# Backlight.net
KiCad netlist of a schematic drawn in Altium Designer
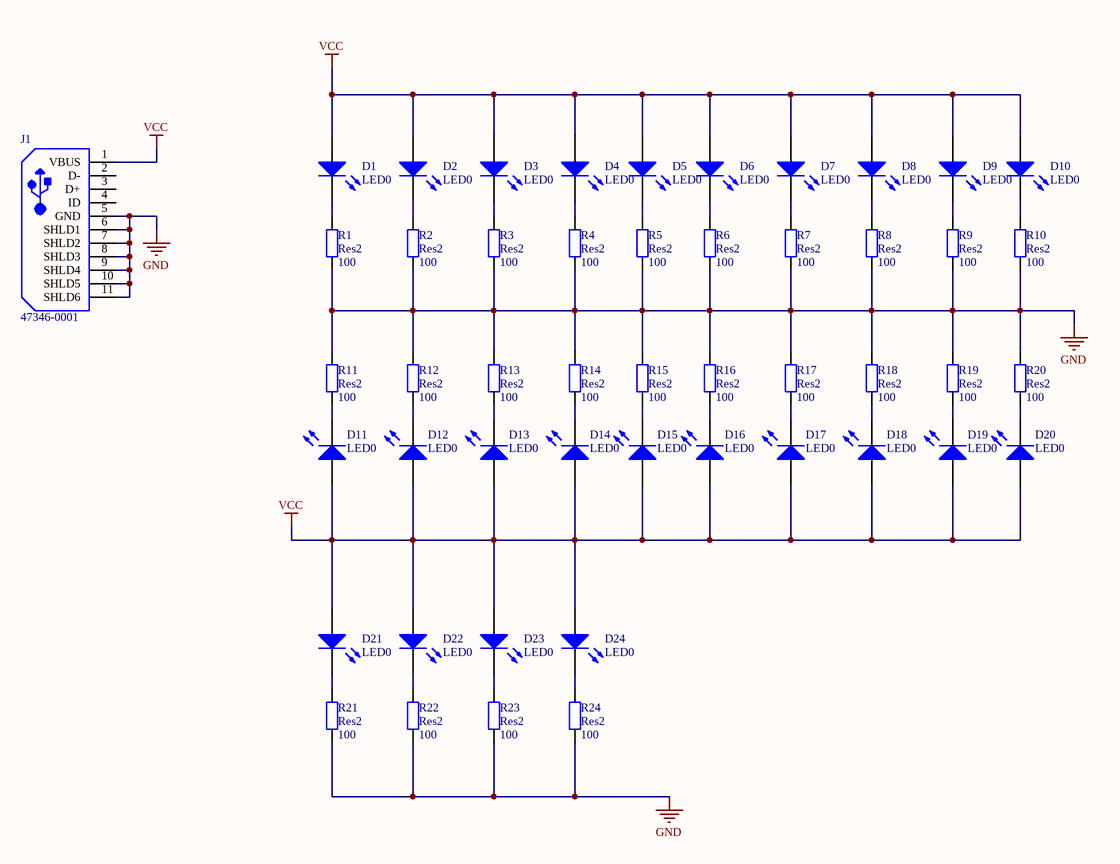
[diagram p0: Backlight.SchDoc]

(export (version "E")
  (design (tool "Eeschema 10.0.6"))
  (components
    (comp (ref "D1")
      (value "LED0")
      (footprint "DIOC2012X06N")
      (description "Typical INFRARED GaAs LED")
      (fields (field (name "PUBLISHER") "Altium Limited"))
      (libsource (lib "Miscellaneous Devices") (part "LED0"))
    )
    (comp (ref "D2")
      (value "LED0")
      (footprint "DIOC2012X06N")
      (description "Typical INFRARED GaAs LED")
      (fields (field (name "PUBLISHER") "Altium Limited"))
      (libsource (lib "Miscellaneous Devices") (part "LED0"))
    )
    (comp (ref "D3")
      (value "LED0")
      (footprint "DIOC2012X06N")
      (description "Typical INFRARED GaAs LED")
      (fields (field (name "PUBLISHER") "Altium Limited"))
      (libsource (lib "Miscellaneous Devices") (part "LED0"))
    )
    (comp (ref "D4")
      (value "LED0")
      (footprint "DIOC2012X06N")
      (description "Typical INFRARED GaAs LED")
      (fields (field (name "PUBLISHER") "Altium Limited"))
      (libsource (lib "Miscellaneous Devices") (part "LED0"))
    )
    (comp (ref "D5")
      (value "LED0")
      (footprint "DIOC2012X06N")
      (description "Typical INFRARED GaAs LED")
      (fields (field (name "PUBLISHER") "Altium Limited"))
      (libsource (lib "Miscellaneous Devices") (part "LED0"))
    )
    (comp (ref "D6")
      (value "LED0")
      (footprint "DIOC2012X06N")
      (description "Typical INFRARED GaAs LED")
      (fields (field (name "PUBLISHER") "Altium Limited"))
      (libsource (lib "Miscellaneous Devices") (part "LED0"))
    )
    (comp (ref "D7")
      (value "LED0")
      (footprint "DIOC2012X06N")
      (description "Typical INFRARED GaAs LED")
      (fields (field (name "PUBLISHER") "Altium Limited"))
      (libsource (lib "Miscellaneous Devices") (part "LED0"))
    )
    (comp (ref "D8")
      (value "LED0")
      (footprint "DIOC2012X06N")
      (description "Typical INFRARED GaAs LED")
      (fields (field (name "PUBLISHER") "Altium Limited"))
      (libsource (lib "Miscellaneous Devices") (part "LED0"))
    )
    (comp (ref "D9")
      (value "LED0")
      (footprint "DIOC2012X06N")
      (description "Typical INFRARED GaAs LED")
      (fields (field (name "PUBLISHER") "Altium Limited"))
      (libsource (lib "Miscellaneous Devices") (part "LED0"))
    )
    (comp (ref "D10")
      (value "LED0")
      (footprint "DIOC2012X06N")
      (description "Typical INFRARED GaAs LED")
      (fields (field (name "PUBLISHER") "Altium Limited"))
      (libsource (lib "Miscellaneous Devices") (part "LED0"))
    )
    (comp (ref "D11")
      (value "LED0")
      (footprint "DIOC2012X06N")
      (description "Typical INFRARED GaAs LED")
      (fields (field (name "PUBLISHER") "Altium Limited"))
      (libsource (lib "Miscellaneous Devices") (part "LED0"))
    )
    (comp (ref "D12")
      (value "LED0")
      (footprint "DIOC2012X06N")
      (description "Typical INFRARED GaAs LED")
      (fields (field (name "PUBLISHER") "Altium Limited"))
      (libsource (lib "Miscellaneous Devices") (part "LED0"))
    )
    (comp (ref "D13")
      (value "LED0")
      (footprint "DIOC2012X06N")
      (description "Typical INFRARED GaAs LED")
      (fields (field (name "PUBLISHER") "Altium Limited"))
      (libsource (lib "Miscellaneous Devices") (part "LED0"))
    )
    (comp (ref "D14")
      (value "LED0")
      (footprint "DIOC2012X06N")
      (description "Typical INFRARED GaAs LED")
      (fields (field (name "PUBLISHER") "Altium Limited"))
      (libsource (lib "Miscellaneous Devices") (part "LED0"))
    )
    (comp (ref "D15")
      (value "LED0")
      (footprint "DIOC2012X06N")
      (description "Typical INFRARED GaAs LED")
      (fields (field (name "PUBLISHER") "Altium Limited"))
      (libsource (lib "Miscellaneous Devices") (part "LED0"))
    )
    (comp (ref "D16")
      (value "LED0")
      (footprint "DIOC2012X06N")
      (description "Typical INFRARED GaAs LED")
      (fields (field (name "PUBLISHER") "Altium Limited"))
      (libsource (lib "Miscellaneous Devices") (part "LED0"))
    )
    (comp (ref "D17")
      (value "LED0")
      (footprint "DIOC2012X06N")
      (description "Typical INFRARED GaAs LED")
      (fields (field (name "PUBLISHER") "Altium Limited"))
      (libsource (lib "Miscellaneous Devices") (part "LED0"))
    )
    (comp (ref "D18")
      (value "LED0")
      (footprint "DIOC2012X06N")
      (description "Typical INFRARED GaAs LED")
      (fields (field (name "PUBLISHER") "Altium Limited"))
      (libsource (lib "Miscellaneous Devices") (part "LED0"))
    )
    (comp (ref "D19")
      (value "LED0")
      (footprint "DIOC2012X06N")
      (description "Typical INFRARED GaAs LED")
      (fields (field (name "PUBLISHER") "Altium Limited"))
      (libsource (lib "Miscellaneous Devices") (part "LED0"))
    )
    (comp (ref "D20")
      (value "LED0")
      (footprint "DIOC2012X06N")
      (description "Typical INFRARED GaAs LED")
      (fields (field (name "PUBLISHER") "Altium Limited"))
      (libsource (lib "Miscellaneous Devices") (part "LED0"))
    )
    (comp (ref "D21")
      (value "LED0")
      (footprint "DIOC2012X06N")
      (description "Typical INFRARED GaAs LED")
      (fields (field (name "PUBLISHER") "Altium Limited"))
      (libsource (lib "Miscellaneous Devices") (part "LED0"))
    )
    (comp (ref "D22")
      (value "LED0")
      (footprint "DIOC2012X06N")
      (description "Typical INFRARED GaAs LED")
      (fields (field (name "PUBLISHER") "Altium Limited"))
      (libsource (lib "Miscellaneous Devices") (part "LED0"))
    )
    (comp (ref "D23")
      (value "LED0")
      (footprint "DIOC2012X06N")
      (description "Typical INFRARED GaAs LED")
      (fields (field (name "PUBLISHER") "Altium Limited"))
      (libsource (lib "Miscellaneous Devices") (part "LED0"))
    )
    (comp (ref "D24")
      (value "LED0")
      (footprint "DIOC2012X06N")
      (description "Typical INFRARED GaAs LED")
      (fields (field (name "PUBLISHER") "Altium Limited"))
      (libsource (lib "Miscellaneous Devices") (part "LED0"))
    )
    (comp (ref "J1")
      (value "47346-0001")
      (footprint "MOLX-47346-0001-5_V")
      (description "Micro-USB B Receptacle with Flange, -30 to 85 degC, 5-Pin SMD, RoHS, Tape and Reel")
      (fields (field (name "MANUFACTURER") "Molex"))
      (libsource (lib "Altium Content Vault") (part "MOLX-47346-0001-5"))
    )
    (comp (ref "R1")
      (value "Res2")
      (footprint "RESC2012X06N")
      (description "Resistor")
      (fields (field (name "ALTIUM_VALUE") "100") (field (name "PUBLISHER") "Altium Limited"))
      (libsource (lib "") (part "Res2_1"))
    )
    (comp (ref "R2")
      (value "Res2")
      (footprint "RESC2012X06N")
      (description "Resistor")
      (fields (field (name "ALTIUM_VALUE") "100") (field (name "PUBLISHER") "Altium Limited"))
      (libsource (lib "") (part "Res2_1"))
    )
    (comp (ref "R3")
      (value "Res2")
      (footprint "RESC2012X06N")
      (description "Resistor")
      (fields (field (name "ALTIUM_VALUE") "100") (field (name "PUBLISHER") "Altium Limited"))
      (libsource (lib "") (part "Res2_1"))
    )
    (comp (ref "R4")
      (value "Res2")
      (footprint "RESC2012X06N")
      (description "Resistor")
      (fields (field (name "ALTIUM_VALUE") "100") (field (name "PUBLISHER") "Altium Limited"))
      (libsource (lib "") (part "Res2_1"))
    )
    (comp (ref "R5")
      (value "Res2")
      (footprint "RESC2012X06N")
      (description "Resistor")
      (fields (field (name "ALTIUM_VALUE") "100") (field (name "PUBLISHER") "Altium Limited"))
      (libsource (lib "") (part "Res2_1"))
    )
    (comp (ref "R6")
      (value "Res2")
      (footprint "RESC2012X06N")
      (description "Resistor")
      (fields (field (name "ALTIUM_VALUE") "100") (field (name "PUBLISHER") "Altium Limited"))
      (libsource (lib "") (part "Res2_1"))
    )
    (comp (ref "R7")
      (value "Res2")
      (footprint "RESC2012X06N")
      (description "Resistor")
      (fields (field (name "ALTIUM_VALUE") "100") (field (name "PUBLISHER") "Altium Limited"))
      (libsource (lib "") (part "Res2_1"))
    )
    (comp (ref "R8")
      (value "Res2")
      (footprint "RESC2012X06N")
      (description "Resistor")
      (fields (field (name "ALTIUM_VALUE") "100") (field (name "PUBLISHER") "Altium Limited"))
      (libsource (lib "") (part "Res2_1"))
    )
    (comp (ref "R9")
      (value "Res2")
      (footprint "RESC2012X06N")
      (description "Resistor")
      (fields (field (name "ALTIUM_VALUE") "100") (field (name "PUBLISHER") "Altium Limited"))
      (libsource (lib "") (part "Res2_1"))
    )
    (comp (ref "R10")
      (value "Res2")
      (footprint "RESC2012X06N")
      (description "Resistor")
      (fields (field (name "ALTIUM_VALUE") "100") (field (name "PUBLISHER") "Altium Limited"))
      (libsource (lib "") (part "Res2_1"))
    )
    (comp (ref "R11")
      (value "Res2")
      (footprint "RESC2012X06N")
      (description "Resistor")
      (fields (field (name "ALTIUM_VALUE") "100") (field (name "PUBLISHER") "Altium Limited"))
      (libsource (lib "Miscellaneous Devices") (part "Res2"))
    )
    (comp (ref "R12")
      (value "Res2")
      (footprint "RESC2012X06N")
      (description "Resistor")
      (fields (field (name "ALTIUM_VALUE") "100") (field (name "PUBLISHER") "Altium Limited"))
      (libsource (lib "Miscellaneous Devices") (part "Res2"))
    )
    (comp (ref "R13")
      (value "Res2")
      (footprint "RESC2012X06N")
      (description "Resistor")
      (fields (field (name "ALTIUM_VALUE") "100") (field (name "PUBLISHER") "Altium Limited"))
      (libsource (lib "Miscellaneous Devices") (part "Res2"))
    )
    (comp (ref "R14")
      (value "Res2")
      (footprint "RESC2012X06N")
      (description "Resistor")
      (fields (field (name "ALTIUM_VALUE") "100") (field (name "PUBLISHER") "Altium Limited"))
      (libsource (lib "Miscellaneous Devices") (part "Res2"))
    )
    (comp (ref "R15")
      (value "Res2")
      (footprint "RESC2012X06N")
      (description "Resistor")
      (fields (field (name "ALTIUM_VALUE") "100") (field (name "PUBLISHER") "Altium Limited"))
      (libsource (lib "Miscellaneous Devices") (part "Res2"))
    )
    (comp (ref "R16")
      (value "Res2")
      (footprint "RESC2012X06N")
      (description "Resistor")
      (fields (field (name "ALTIUM_VALUE") "100") (field (name "PUBLISHER") "Altium Limited"))
      (libsource (lib "Miscellaneous Devices") (part "Res2"))
    )
    (comp (ref "R17")
      (value "Res2")
      (footprint "RESC2012X06N")
      (description "Resistor")
      (fields (field (name "ALTIUM_VALUE") "100") (field (name "PUBLISHER") "Altium Limited"))
      (libsource (lib "Miscellaneous Devices") (part "Res2"))
    )
    (comp (ref "R18")
      (value "Res2")
      (footprint "RESC2012X06N")
      (description "Resistor")
      (fields (field (name "ALTIUM_VALUE") "100") (field (name "PUBLISHER") "Altium Limited"))
      (libsource (lib "Miscellaneous Devices") (part "Res2"))
    )
    (comp (ref "R19")
      (value "Res2")
      (footprint "RESC2012X06N")
      (description "Resistor")
      (fields (field (name "ALTIUM_VALUE") "100") (field (name "PUBLISHER") "Altium Limited"))
      (libsource (lib "Miscellaneous Devices") (part "Res2"))
    )
    (comp (ref "R20")
      (value "Res2")
      (footprint "RESC2012X06N")
      (description "Resistor")
      (fields (field (name "ALTIUM_VALUE") "100") (field (name "PUBLISHER") "Altium Limited"))
      (libsource (lib "Miscellaneous Devices") (part "Res2"))
    )
    (comp (ref "R21")
      (value "Res2")
      (footprint "RESC2012X06N")
      (description "Resistor")
      (fields (field (name "ALTIUM_VALUE") "100") (field (name "PUBLISHER") "Altium Limited"))
      (libsource (lib "") (part "Res2_1"))
    )
    (comp (ref "R22")
      (value "Res2")
      (footprint "RESC2012X06N")
      (description "Resistor")
      (fields (field (name "ALTIUM_VALUE") "100") (field (name "PUBLISHER") "Altium Limited"))
      (libsource (lib "") (part "Res2_1"))
    )
    (comp (ref "R23")
      (value "Res2")
      (footprint "RESC2012X06N")
      (description "Resistor")
      (fields (field (name "ALTIUM_VALUE") "100") (field (name "PUBLISHER") "Altium Limited"))
      (libsource (lib "") (part "Res2_1"))
    )
    (comp (ref "R24")
      (value "Res2")
      (footprint "RESC2012X06N")
      (description "Resistor")
      (fields (field (name "ALTIUM_VALUE") "100") (field (name "PUBLISHER") "Altium Limited"))
      (libsource (lib "") (part "Res2_1"))
    )
  )
  (nets
    (net (code "1") (name "GND") (class "Default")
      (node (ref "J1") (pin "10") (pinfunction "SHLD5_10") (pintype "passive"))
      (node (ref "J1") (pin "11") (pinfunction "SHLD6_11") (pintype "passive"))
      (node (ref "J1") (pin "5") (pinfunction "GND_5") (pintype "passive"))
      (node (ref "J1") (pin "6") (pinfunction "SHLD1_6") (pintype "passive"))
      (node (ref "J1") (pin "7") (pinfunction "SHLD2_7") (pintype "passive"))
      (node (ref "J1") (pin "8") (pinfunction "SHLD3_8") (pintype "passive"))
      (node (ref "J1") (pin "9") (pinfunction "SHLD4_9") (pintype "passive"))
      (node (ref "R1") (pin "1") (pinfunction "1_1") (pintype "passive"))
      (node (ref "R10") (pin "1") (pinfunction "1_1") (pintype "passive"))
      (node (ref "R11") (pin "1") (pinfunction "1_1") (pintype "passive"))
      (node (ref "R12") (pin "1") (pinfunction "1_1") (pintype "passive"))
      (node (ref "R13") (pin "1") (pinfunction "1_1") (pintype "passive"))
      (node (ref "R14") (pin "1") (pinfunction "1_1") (pintype "passive"))
      (node (ref "R15") (pin "1") (pinfunction "1_1") (pintype "passive"))
      (node (ref "R16") (pin "1") (pinfunction "1_1") (pintype "passive"))
      (node (ref "R17") (pin "1") (pinfunction "1_1") (pintype "passive"))
      (node (ref "R18") (pin "1") (pinfunction "1_1") (pintype "passive"))
      (node (ref "R19") (pin "1") (pinfunction "1_1") (pintype "passive"))
      (node (ref "R2") (pin "1") (pinfunction "1_1") (pintype "passive"))
      (node (ref "R20") (pin "1") (pinfunction "1_1") (pintype "passive"))
      (node (ref "R21") (pin "1") (pinfunction "1_1") (pintype "passive"))
      (node (ref "R22") (pin "1") (pinfunction "1_1") (pintype "passive"))
      (node (ref "R23") (pin "1") (pinfunction "1_1") (pintype "passive"))
      (node (ref "R24") (pin "1") (pinfunction "1_1") (pintype "passive"))
      (node (ref "R3") (pin "1") (pinfunction "1_1") (pintype "passive"))
      (node (ref "R4") (pin "1") (pinfunction "1_1") (pintype "passive"))
      (node (ref "R5") (pin "1") (pinfunction "1_1") (pintype "passive"))
      (node (ref "R6") (pin "1") (pinfunction "1_1") (pintype "passive"))
      (node (ref "R7") (pin "1") (pinfunction "1_1") (pintype "passive"))
      (node (ref "R8") (pin "1") (pinfunction "1_1") (pintype "passive"))
      (node (ref "R9") (pin "1") (pinfunction "1_1") (pintype "passive"))
    )
    (net (code "2") (name "Net-(D1-K)") (class "Default")
      (node (ref "D1") (pin "2") (pinfunction "K_2") (pintype "passive"))
      (node (ref "R1") (pin "2") (pinfunction "2_2") (pintype "passive"))
    )
    (net (code "3") (name "Net-(D2-K)") (class "Default")
      (node (ref "D2") (pin "2") (pinfunction "K_2") (pintype "passive"))
      (node (ref "R2") (pin "2") (pinfunction "2_2") (pintype "passive"))
    )
    (net (code "4") (name "Net-(D3-K)") (class "Default")
      (node (ref "D3") (pin "2") (pinfunction "K_2") (pintype "passive"))
      (node (ref "R3") (pin "2") (pinfunction "2_2") (pintype "passive"))
    )
    (net (code "5") (name "Net-(D4-K)") (class "Default")
      (node (ref "D4") (pin "2") (pinfunction "K_2") (pintype "passive"))
      (node (ref "R4") (pin "2") (pinfunction "2_2") (pintype "passive"))
    )
    (net (code "6") (name "Net-(D5-K)") (class "Default")
      (node (ref "D5") (pin "2") (pinfunction "K_2") (pintype "passive"))
      (node (ref "R5") (pin "2") (pinfunction "2_2") (pintype "passive"))
    )
    (net (code "7") (name "Net-(D6-K)") (class "Default")
      (node (ref "D6") (pin "2") (pinfunction "K_2") (pintype "passive"))
      (node (ref "R6") (pin "2") (pinfunction "2_2") (pintype "passive"))
    )
    (net (code "8") (name "Net-(D7-K)") (class "Default")
      (node (ref "D7") (pin "2") (pinfunction "K_2") (pintype "passive"))
      (node (ref "R7") (pin "2") (pinfunction "2_2") (pintype "passive"))
    )
    (net (code "9") (name "Net-(D8-K)") (class "Default")
      (node (ref "D8") (pin "2") (pinfunction "K_2") (pintype "passive"))
      (node (ref "R8") (pin "2") (pinfunction "2_2") (pintype "passive"))
    )
    (net (code "10") (name "Net-(D9-K)") (class "Default")
      (node (ref "D9") (pin "2") (pinfunction "K_2") (pintype "passive"))
      (node (ref "R9") (pin "2") (pinfunction "2_2") (pintype "passive"))
    )
    (net (code "11") (name "Net-(D10-K)") (class "Default")
      (node (ref "D10") (pin "2") (pinfunction "K_2") (pintype "passive"))
      (node (ref "R10") (pin "2") (pinfunction "2_2") (pintype "passive"))
    )
    (net (code "12") (name "Net-(D11-K)") (class "Default")
      (node (ref "D11") (pin "2") (pinfunction "K_2") (pintype "passive"))
      (node (ref "R11") (pin "2") (pinfunction "2_2") (pintype "passive"))
    )
    (net (code "13") (name "Net-(D12-K)") (class "Default")
      (node (ref "D12") (pin "2") (pinfunction "K_2") (pintype "passive"))
      (node (ref "R12") (pin "2") (pinfunction "2_2") (pintype "passive"))
    )
    (net (code "14") (name "Net-(D13-K)") (class "Default")
      (node (ref "D13") (pin "2") (pinfunction "K_2") (pintype "passive"))
      (node (ref "R13") (pin "2") (pinfunction "2_2") (pintype "passive"))
    )
    (net (code "15") (name "Net-(D14-K)") (class "Default")
      (node (ref "D14") (pin "2") (pinfunction "K_2") (pintype "passive"))
      (node (ref "R14") (pin "2") (pinfunction "2_2") (pintype "passive"))
    )
    (net (code "16") (name "Net-(D15-K)") (class "Default")
      (node (ref "D15") (pin "2") (pinfunction "K_2") (pintype "passive"))
      (node (ref "R15") (pin "2") (pinfunction "2_2") (pintype "passive"))
    )
    (net (code "17") (name "Net-(D16-K)") (class "Default")
      (node (ref "D16") (pin "2") (pinfunction "K_2") (pintype "passive"))
      (node (ref "R16") (pin "2") (pinfunction "2_2") (pintype "passive"))
    )
    (net (code "18") (name "Net-(D17-K)") (class "Default")
      (node (ref "D17") (pin "2") (pinfunction "K_2") (pintype "passive"))
      (node (ref "R17") (pin "2") (pinfunction "2_2") (pintype "passive"))
    )
    (net (code "19") (name "Net-(D18-K)") (class "Default")
      (node (ref "D18") (pin "2") (pinfunction "K_2") (pintype "passive"))
      (node (ref "R18") (pin "2") (pinfunction "2_2") (pintype "passive"))
    )
    (net (code "20") (name "Net-(D19-K)") (class "Default")
      (node (ref "D19") (pin "2") (pinfunction "K_2") (pintype "passive"))
      (node (ref "R19") (pin "2") (pinfunction "2_2") (pintype "passive"))
    )
    (net (code "21") (name "Net-(D20-K)") (class "Default")
      (node (ref "D20") (pin "2") (pinfunction "K_2") (pintype "passive"))
      (node (ref "R20") (pin "2") (pinfunction "2_2") (pintype "passive"))
    )
    (net (code "22") (name "Net-(D21-K)") (class "Default")
      (node (ref "D21") (pin "2") (pinfunction "K_2") (pintype "passive"))
      (node (ref "R21") (pin "2") (pinfunction "2_2") (pintype "passive"))
    )
    (net (code "23") (name "Net-(D22-K)") (class "Default")
      (node (ref "D22") (pin "2") (pinfunction "K_2") (pintype "passive"))
      (node (ref "R22") (pin "2") (pinfunction "2_2") (pintype "passive"))
    )
    (net (code "24") (name "Net-(D23-K)") (class "Default")
      (node (ref "D23") (pin "2") (pinfunction "K_2") (pintype "passive"))
      (node (ref "R23") (pin "2") (pinfunction "2_2") (pintype "passive"))
    )
    (net (code "25") (name "Net-(D24-K)") (class "Default")
      (node (ref "D24") (pin "2") (pinfunction "K_2") (pintype "passive"))
      (node (ref "R24") (pin "2") (pinfunction "2_2") (pintype "passive"))
    )
    (net (code "26") (name "VCC") (class "Default")
      (node (ref "D1") (pin "1") (pinfunction "A_1") (pintype "passive"))
      (node (ref "D10") (pin "1") (pinfunction "A_1") (pintype "passive"))
      (node (ref "D11") (pin "1") (pinfunction "A_1") (pintype "passive"))
      (node (ref "D12") (pin "1") (pinfunction "A_1") (pintype "passive"))
      (node (ref "D13") (pin "1") (pinfunction "A_1") (pintype "passive"))
      (node (ref "D14") (pin "1") (pinfunction "A_1") (pintype "passive"))
      (node (ref "D15") (pin "1") (pinfunction "A_1") (pintype "passive"))
      (node (ref "D16") (pin "1") (pinfunction "A_1") (pintype "passive"))
      (node (ref "D17") (pin "1") (pinfunction "A_1") (pintype "passive"))
      (node (ref "D18") (pin "1") (pinfunction "A_1") (pintype "passive"))
      (node (ref "D19") (pin "1") (pinfunction "A_1") (pintype "passive"))
      (node (ref "D2") (pin "1") (pinfunction "A_1") (pintype "passive"))
      (node (ref "D20") (pin "1") (pinfunction "A_1") (pintype "passive"))
      (node (ref "D21") (pin "1") (pinfunction "A_1") (pintype "passive"))
      (node (ref "D22") (pin "1") (pinfunction "A_1") (pintype "passive"))
      (node (ref "D23") (pin "1") (pinfunction "A_1") (pintype "passive"))
      (node (ref "D24") (pin "1") (pinfunction "A_1") (pintype "passive"))
      (node (ref "D3") (pin "1") (pinfunction "A_1") (pintype "passive"))
      (node (ref "D4") (pin "1") (pinfunction "A_1") (pintype "passive"))
      (node (ref "D5") (pin "1") (pinfunction "A_1") (pintype "passive"))
      (node (ref "D6") (pin "1") (pinfunction "A_1") (pintype "passive"))
      (node (ref "D7") (pin "1") (pinfunction "A_1") (pintype "passive"))
      (node (ref "D8") (pin "1") (pinfunction "A_1") (pintype "passive"))
      (node (ref "D9") (pin "1") (pinfunction "A_1") (pintype "passive"))
      (node (ref "J1") (pin "1") (pinfunction "VBUS_1") (pintype "passive"))
    )
    (net (code "27") (name "unconnected-(J1-D+-Pad3)") (class "Default")
      (node (ref "J1") (pin "3") (pinfunction "D+_3") (pintype "passive"))
    )
    (net (code "28") (name "unconnected-(J1-D--Pad2)") (class "Default")
      (node (ref "J1") (pin "2") (pinfunction "D-_2") (pintype "passive"))
    )
    (net (code "29") (name "unconnected-(J1-ID-Pad4)") (class "Default")
      (node (ref "J1") (pin "4") (pinfunction "ID_4") (pintype "passive"))
    )
  )
)
